# PDB_MH.net
KiCad netlist of a schematic drawn in EAGLE
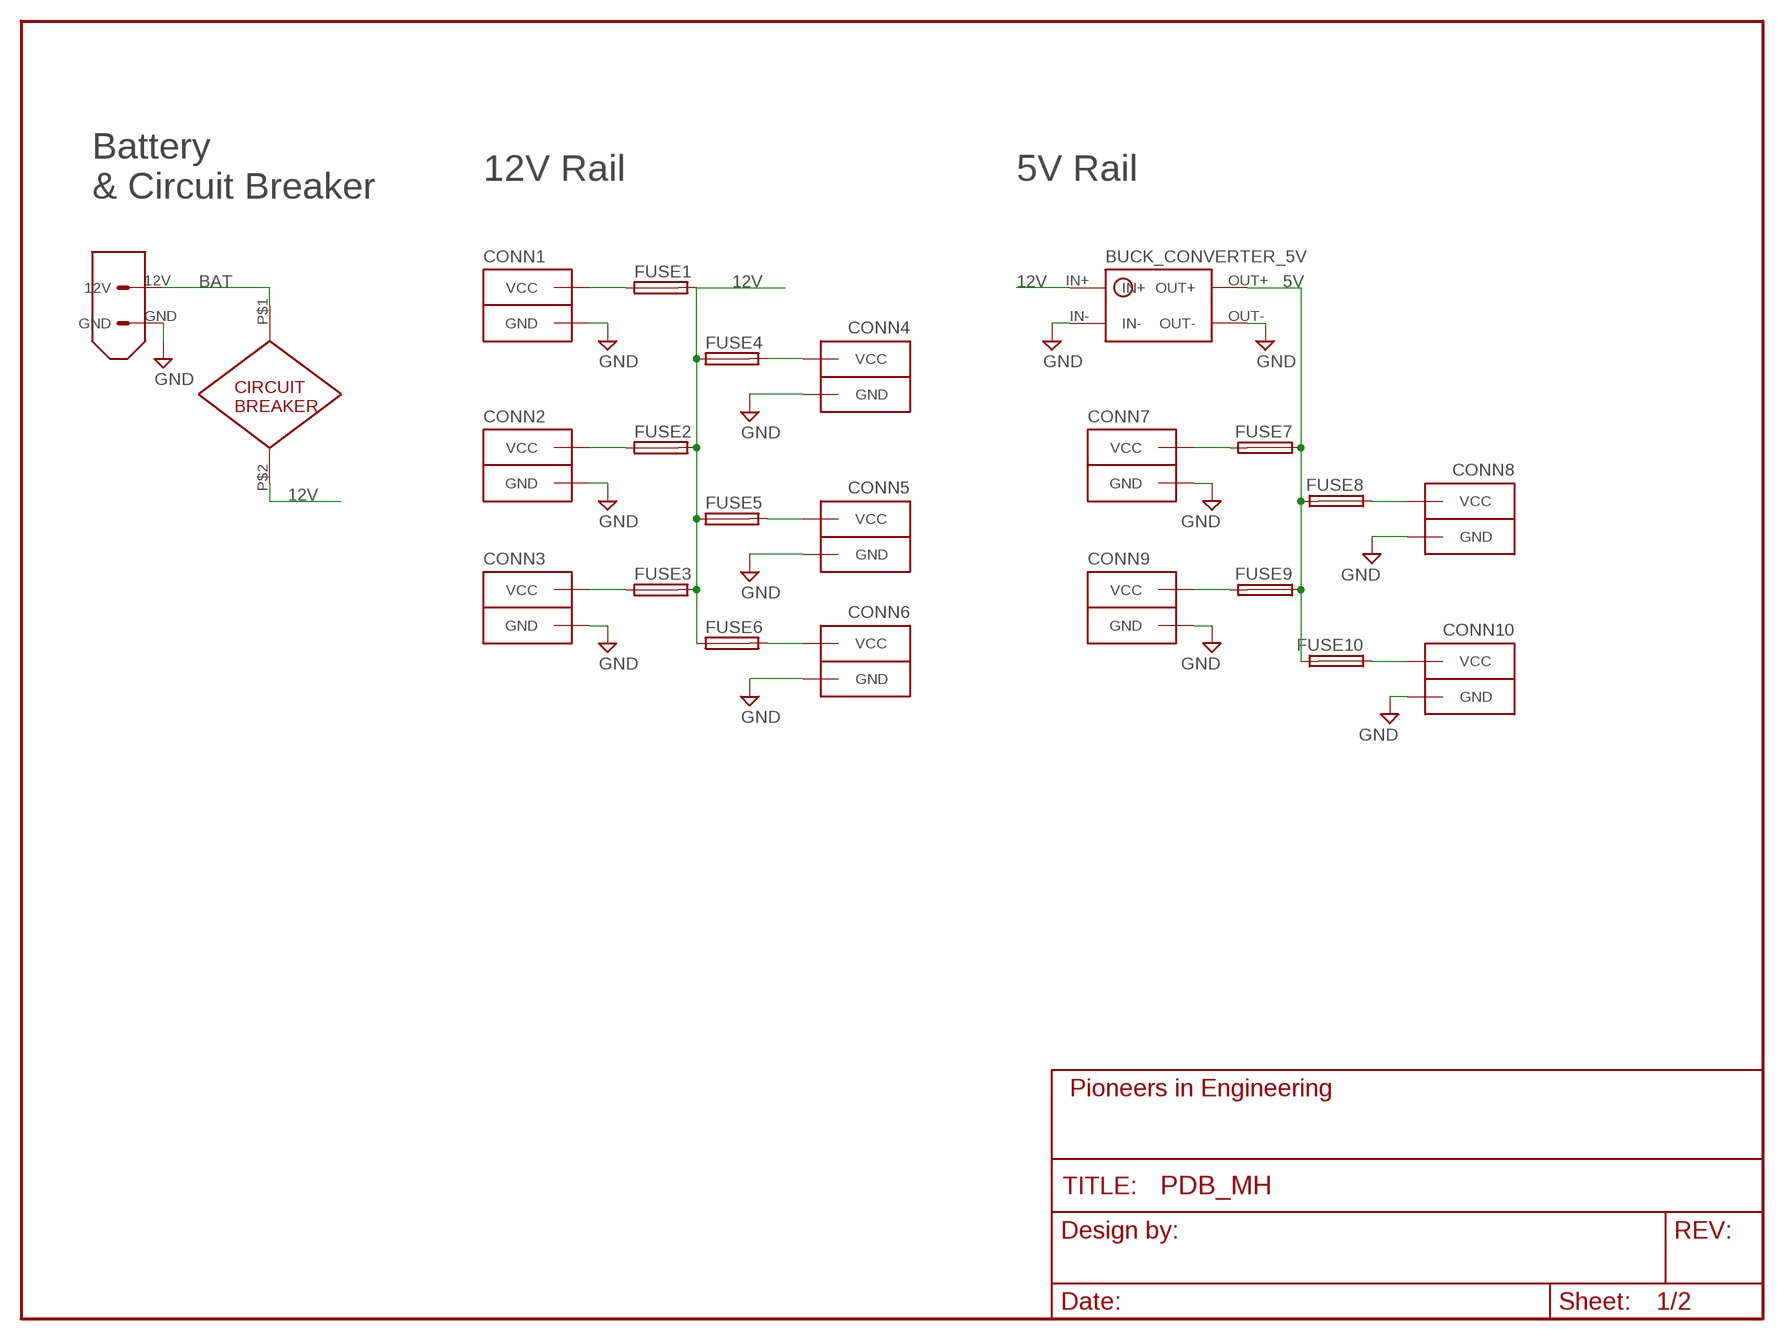
[diagram p0: schematic, sheet 1]
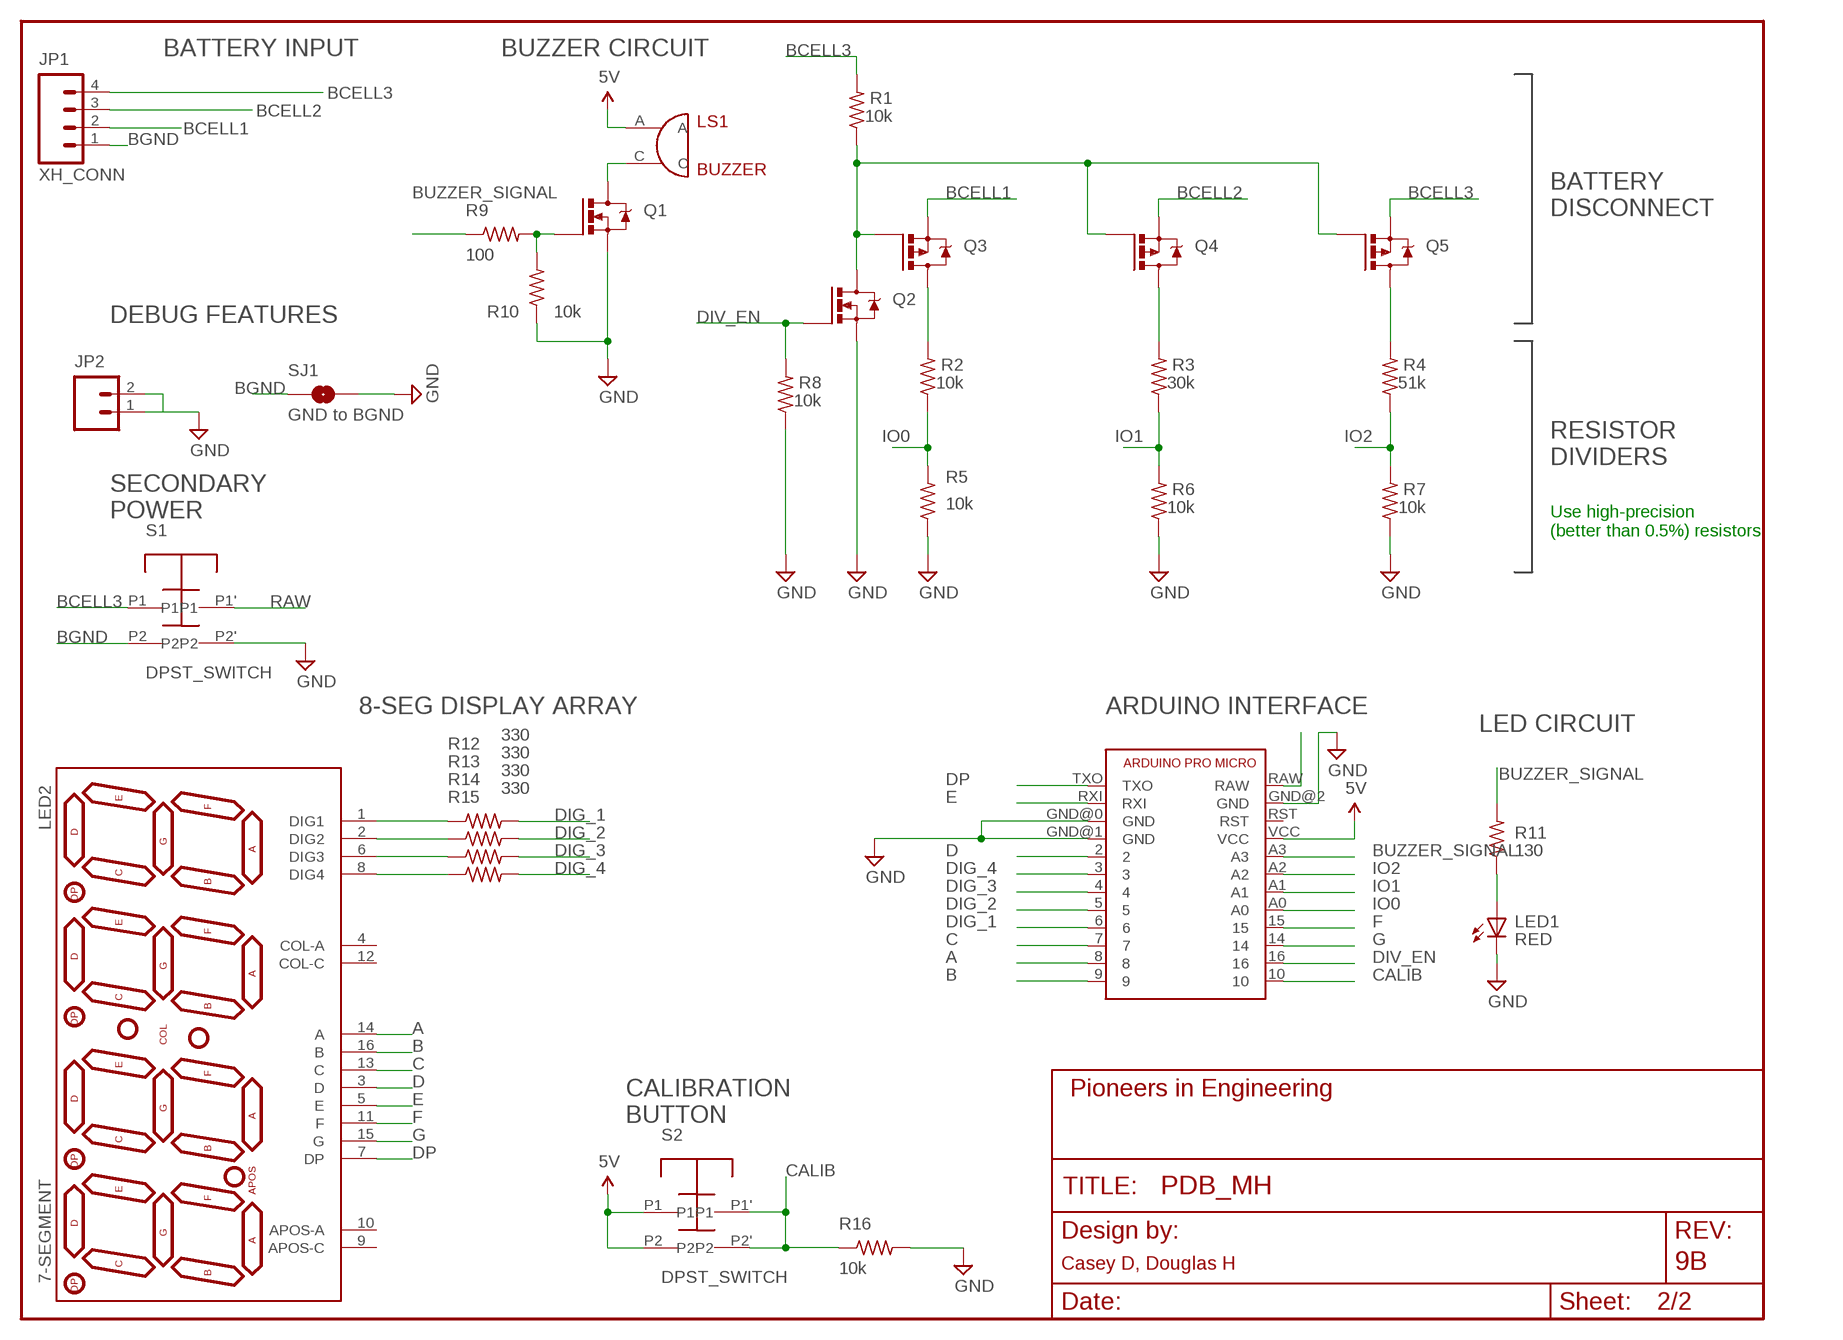
[diagram p1: schematic, sheet 2]

(export (version "E")
  (design (tool "Eeschema 10.0.6"))
  (components
    (comp (ref "CIRCUIT_BREAKER")
      (value "CIRC_BREAKER")
      (footprint "eagle-import:CIRC_BREAKER")
      (libsource (lib "eagle-import") (part "CIRC_BREAKER"))
    )
    (comp (ref "CONN1")
      (value "ANDERSONVERTICAL")
      (footprint "eagle-import:ANDERSON_VERTICAL")
      (libsource (lib "eagle-import") (part "ANDERSONVERTICAL"))
    )
    (comp (ref "CONN2")
      (value "ANDERSONVERTICAL")
      (footprint "eagle-import:ANDERSON_VERTICAL")
      (libsource (lib "eagle-import") (part "ANDERSONVERTICAL"))
    )
    (comp (ref "CONN3")
      (value "ANDERSONVERTICAL")
      (footprint "eagle-import:ANDERSON_VERTICAL")
      (libsource (lib "eagle-import") (part "ANDERSONVERTICAL"))
    )
    (comp (ref "CONN4")
      (value "ANDERSONVERTICAL")
      (footprint "eagle-import:ANDERSON_VERTICAL")
      (libsource (lib "eagle-import") (part "ANDERSONVERTICAL"))
    )
    (comp (ref "CONN5")
      (value "ANDERSONVERTICAL")
      (footprint "eagle-import:ANDERSON_VERTICAL")
      (libsource (lib "eagle-import") (part "ANDERSONVERTICAL"))
    )
    (comp (ref "CONN6")
      (value "ANDERSONVERTICAL")
      (footprint "eagle-import:ANDERSON_VERTICAL")
      (libsource (lib "eagle-import") (part "ANDERSONVERTICAL"))
    )
    (comp (ref "CONN7")
      (value "ANDERSONVERTICAL")
      (footprint "eagle-import:ANDERSON_VERTICAL")
      (libsource (lib "eagle-import") (part "ANDERSONVERTICAL"))
    )
    (comp (ref "CONN8")
      (value "ANDERSONVERTICAL")
      (footprint "eagle-import:ANDERSON_VERTICAL")
      (libsource (lib "eagle-import") (part "ANDERSONVERTICAL"))
    )
    (comp (ref "CONN9")
      (value "ANDERSONVERTICAL")
      (footprint "eagle-import:ANDERSON_VERTICAL")
      (libsource (lib "eagle-import") (part "ANDERSONVERTICAL"))
    )
    (comp (ref "CONN10")
      (value "ANDERSONVERTICAL")
      (footprint "eagle-import:ANDERSON_VERTICAL")
      (libsource (lib "eagle-import") (part "ANDERSONVERTICAL"))
    )
    (comp (ref "FUSE1")
      (value "FUSE_HOLDER_SMD")
      (footprint "eagle-import:FUSE_HOLDER_SMD")
      (libsource (lib "eagle-import") (part "FUSE_HOLDER_SMD"))
    )
    (comp (ref "FUSE2")
      (value "FUSE_HOLDER_SMD")
      (footprint "eagle-import:FUSE_HOLDER_SMD")
      (libsource (lib "eagle-import") (part "FUSE_HOLDER_SMD"))
    )
    (comp (ref "FUSE3")
      (value "FUSE_HOLDER_SMD")
      (footprint "eagle-import:FUSE_HOLDER_SMD")
      (libsource (lib "eagle-import") (part "FUSE_HOLDER_SMD"))
    )
    (comp (ref "FUSE4")
      (value "FUSE_HOLDER_SMD")
      (footprint "eagle-import:FUSE_HOLDER_SMD")
      (libsource (lib "eagle-import") (part "FUSE_HOLDER_SMD"))
    )
    (comp (ref "FUSE5")
      (value "FUSE_HOLDER_SMD")
      (footprint "eagle-import:FUSE_HOLDER_SMD")
      (libsource (lib "eagle-import") (part "FUSE_HOLDER_SMD"))
    )
    (comp (ref "FUSE6")
      (value "FUSE_HOLDER_SMD")
      (footprint "eagle-import:FUSE_HOLDER_SMD")
      (libsource (lib "eagle-import") (part "FUSE_HOLDER_SMD"))
    )
    (comp (ref "FUSE7")
      (value "FUSE_HOLDER_SMD")
      (footprint "eagle-import:FUSE_HOLDER_SMD")
      (libsource (lib "eagle-import") (part "FUSE_HOLDER_SMD"))
    )
    (comp (ref "FUSE8")
      (value "FUSE_HOLDER_SMD")
      (footprint "eagle-import:FUSE_HOLDER_SMD")
      (libsource (lib "eagle-import") (part "FUSE_HOLDER_SMD"))
    )
    (comp (ref "FUSE9")
      (value "FUSE_HOLDER_SMD")
      (footprint "eagle-import:FUSE_HOLDER_SMD")
      (libsource (lib "eagle-import") (part "FUSE_HOLDER_SMD"))
    )
    (comp (ref "FUSE10")
      (value "FUSE_HOLDER_SMD")
      (footprint "eagle-import:FUSE_HOLDER_SMD")
      (libsource (lib "eagle-import") (part "FUSE_HOLDER_SMD"))
    )
    (comp (ref "U$7")
      (value "BUCK_CONVERTER_5V")
      (footprint "eagle-import:BUCK_CONVERTER_5V")
      (libsource (lib "eagle-import") (part "BUCK_CONVERTER_5V"))
    )
    (comp (ref "XT60")
      (value "XT60CONNECTOR")
      (footprint "eagle-import:XT60CONNECTOR")
      (fields (field (name "PARTNUMBER") "PRT-10474 "))
      (libsource (lib "eagle-import") (part "XT60CONNECTOR"))
    )
    (comp (ref "JP1")
      (value "XH_CONN")
      (footprint "eagle-import:XH_CONNECTOR_4POS_2.5MM")
      (libsource (lib "eagle-import") (part "XH_CONNECTOR_4POS"))
    )
    (comp (ref "JP2")
      (value "M02PTH")
      (footprint "eagle-import:1X02")
      (libsource (lib "eagle-import") (part "M02PTH"))
    )
    (comp (ref "LED1")
      (value "RED")
      (footprint "eagle-import:LED-0805")
      (libsource (lib "eagle-import") (part "LED0805"))
    )
    (comp (ref "LED2")
      (value "7-SEGMENT")
      (footprint "eagle-import:7-SEGMENT-4DIGIT-YOUNGSUN")
      (libsource (lib "eagle-import") (part "7-SEGMENT-4DIGIT-YOUNGSUN"))
    )
    (comp (ref "LS1")
      (value "BUZZER")
      (footprint "eagle-import:BUZZER_MAGNETIC_5V_12MM_RADIAL")
      (libsource (lib "eagle-import") (part "BUZZER"))
    )
    (comp (ref "Q1")
      (value "IRFML8244")
      (footprint "eagle-import:SOT23-3")
      (libsource (lib "eagle-import") (part "N-CHANNEL-MOSFETSOT23-3"))
    )
    (comp (ref "Q2")
      (value "IRFML8244")
      (footprint "eagle-import:SOT23-3")
      (libsource (lib "eagle-import") (part "N-CHANNEL-MOSFETSOT23-3"))
    )
    (comp (ref "Q3")
      (value "PMOSFET")
      (footprint "eagle-import:SOT23-3")
      (libsource (lib "eagle-import") (part "P-CHANNEL-MOSFETSOT23-3"))
    )
    (comp (ref "Q4")
      (value "P-CHANNEL-MOSFETSOT23-3")
      (footprint "eagle-import:SOT23-3")
      (libsource (lib "eagle-import") (part "P-CHANNEL-MOSFETSOT23-3"))
    )
    (comp (ref "Q5")
      (value "P-CHANNEL-MOSFETSOT23-3")
      (footprint "eagle-import:SOT23-3")
      (libsource (lib "eagle-import") (part "P-CHANNEL-MOSFETSOT23-3"))
    )
    (comp (ref "R1")
      (value "10k")
      (footprint "eagle-import:R0603")
      (libsource (lib "eagle-import") (part "R-US_R0603"))
    )
    (comp (ref "R2")
      (value "10k")
      (footprint "eagle-import:R0603")
      (libsource (lib "eagle-import") (part "R-US_R0603"))
    )
    (comp (ref "R3")
      (value "30k")
      (footprint "eagle-import:R0603")
      (libsource (lib "eagle-import") (part "R-US_R0603"))
    )
    (comp (ref "R4")
      (value "51k")
      (footprint "eagle-import:R0603")
      (libsource (lib "eagle-import") (part "R-US_R0603"))
    )
    (comp (ref "R5")
      (value "10k")
      (footprint "eagle-import:R0603")
      (libsource (lib "eagle-import") (part "R-US_R0603"))
    )
    (comp (ref "R6")
      (value "10k")
      (footprint "eagle-import:R0603")
      (libsource (lib "eagle-import") (part "R-US_R0603"))
    )
    (comp (ref "R7")
      (value "10k")
      (footprint "eagle-import:R0603")
      (libsource (lib "eagle-import") (part "R-US_R0603"))
    )
    (comp (ref "R8")
      (value "10k")
      (footprint "eagle-import:R0603")
      (libsource (lib "eagle-import") (part "R-US_R0603"))
    )
    (comp (ref "R9")
      (value "100")
      (footprint "eagle-import:R0603")
      (libsource (lib "eagle-import") (part "R-US_R0603"))
    )
    (comp (ref "R10")
      (value "10k")
      (footprint "eagle-import:R0603")
      (libsource (lib "eagle-import") (part "R-US_R0603"))
    )
    (comp (ref "R11")
      (value "130")
      (footprint "eagle-import:R0603")
      (libsource (lib "eagle-import") (part "R-US_R0603"))
    )
    (comp (ref "R12")
      (value "330")
      (footprint "eagle-import:R0603")
      (libsource (lib "eagle-import") (part "R-US_R0603"))
    )
    (comp (ref "R13")
      (value "330")
      (footprint "eagle-import:R0603")
      (libsource (lib "eagle-import") (part "R-US_R0603"))
    )
    (comp (ref "R14")
      (value "330")
      (footprint "eagle-import:R0603")
      (libsource (lib "eagle-import") (part "R-US_R0603"))
    )
    (comp (ref "R15")
      (value "330")
      (footprint "eagle-import:R0603")
      (libsource (lib "eagle-import") (part "R-US_R0603"))
    )
    (comp (ref "R16")
      (value "10k")
      (footprint "eagle-import:R0603")
      (libsource (lib "eagle-import") (part "R-US_R0603"))
    )
    (comp (ref "S1")
      (value "DPST_SWITCH")
      (footprint "eagle-import:C&K_SWITCH")
      (libsource (lib "eagle-import") (part "DPST_SWITCH"))
    )
    (comp (ref "S2")
      (value "DPST_SWITCH")
      (footprint "eagle-import:C&K_SWITCH")
      (libsource (lib "eagle-import") (part "DPST_SWITCH"))
    )
    (comp (ref "SJ1")
      (value "GND to BGND")
      (footprint "eagle-import:SJ_2S-NO")
      (libsource (lib "eagle-import") (part "SOLDERJUMPERNO"))
    )
    (comp (ref "UC1")
      (value "ARDUINO_PRO_MICRO")
      (footprint "eagle-import:ARDUINO_PRO_MICRO")
      (libsource (lib "eagle-import") (part "ARDUINO_PRO_MICRO"))
    )
  )
  (nets
    (net (code "1") (name "5V") (class "Default")
      (node (ref "FUSE10") (pin "P$2_DOWN") (pinfunction "2_P$2_DOWN") (pintype "passive"))
      (node (ref "FUSE10") (pin "P$2_UP") (pinfunction "2_P$2_UP") (pintype "passive"))
      (node (ref "FUSE7") (pin "P$1_DOWN") (pinfunction "1_P$1_DOWN") (pintype "passive"))
      (node (ref "FUSE7") (pin "P$1_UP") (pinfunction "1_P$1_UP") (pintype "passive"))
      (node (ref "FUSE8") (pin "P$2_DOWN") (pinfunction "2_P$2_DOWN") (pintype "passive"))
      (node (ref "FUSE8") (pin "P$2_UP") (pinfunction "2_P$2_UP") (pintype "passive"))
      (node (ref "FUSE9") (pin "P$1_DOWN") (pinfunction "1_P$1_DOWN") (pintype "passive"))
      (node (ref "FUSE9") (pin "P$1_UP") (pinfunction "1_P$1_UP") (pintype "passive"))
      (node (ref "LS1") (pin "A") (pinfunction "A_A") (pintype "bidirectional"))
      (node (ref "S2") (pin "P1") (pinfunction "P1_P1") (pintype "bidirectional"))
      (node (ref "S2") (pin "P2") (pinfunction "P2_P2") (pintype "bidirectional"))
      (node (ref "U$7") (pin "OUT+") (pinfunction "OUT+_OUT+") (pintype "bidirectional"))
      (node (ref "UC1") (pin "VCC") (pinfunction "VCC_VCC") (pintype "bidirectional"))
    )
    (net (code "2") (name "12V") (class "Default")
      (node (ref "CIRCUIT_BREAKER") (pin "P$2") (pinfunction "P$2_P$2") (pintype "bidirectional"))
      (node (ref "FUSE1") (pin "P$2_DOWN") (pinfunction "2_P$2_DOWN") (pintype "passive"))
      (node (ref "FUSE1") (pin "P$2_UP") (pinfunction "2_P$2_UP") (pintype "passive"))
      (node (ref "FUSE2") (pin "P$2_DOWN") (pinfunction "2_P$2_DOWN") (pintype "passive"))
      (node (ref "FUSE2") (pin "P$2_UP") (pinfunction "2_P$2_UP") (pintype "passive"))
      (node (ref "FUSE3") (pin "P$2_DOWN") (pinfunction "2_P$2_DOWN") (pintype "passive"))
      (node (ref "FUSE3") (pin "P$2_UP") (pinfunction "2_P$2_UP") (pintype "passive"))
      (node (ref "FUSE4") (pin "P$1_DOWN") (pinfunction "1_P$1_DOWN") (pintype "passive"))
      (node (ref "FUSE4") (pin "P$1_UP") (pinfunction "1_P$1_UP") (pintype "passive"))
      (node (ref "FUSE5") (pin "P$1_DOWN") (pinfunction "1_P$1_DOWN") (pintype "passive"))
      (node (ref "FUSE5") (pin "P$1_UP") (pinfunction "1_P$1_UP") (pintype "passive"))
      (node (ref "FUSE6") (pin "P$1_DOWN") (pinfunction "1_P$1_DOWN") (pintype "passive"))
      (node (ref "FUSE6") (pin "P$1_UP") (pinfunction "1_P$1_UP") (pintype "passive"))
      (node (ref "U$7") (pin "IN+") (pinfunction "IN+_IN+") (pintype "bidirectional"))
    )
    (net (code "3") (name "A") (class "Default")
      (node (ref "LED2") (pin "14") (pinfunction "A_14") (pintype "bidirectional"))
      (node (ref "UC1") (pin "8") (pinfunction "8_8") (pintype "bidirectional"))
    )
    (net (code "4") (name "B") (class "Default")
      (node (ref "LED2") (pin "16") (pinfunction "B_16") (pintype "bidirectional"))
      (node (ref "UC1") (pin "9") (pinfunction "9_9") (pintype "bidirectional"))
    )
    (net (code "5") (name "BAT") (class "Default")
      (node (ref "CIRCUIT_BREAKER") (pin "P$1") (pinfunction "P$1_P$1") (pintype "bidirectional"))
      (node (ref "XT60") (pin "12V") (pinfunction "12V_12V") (pintype "bidirectional"))
    )
    (net (code "6") (name "BCELL1") (class "Default")
      (node (ref "JP1") (pin "2") (pinfunction "2_2") (pintype "passive"))
      (node (ref "Q3") (pin "2") (pinfunction "S_2") (pintype "passive"))
    )
    (net (code "7") (name "BCELL2") (class "Default")
      (node (ref "JP1") (pin "3") (pinfunction "3_3") (pintype "passive"))
      (node (ref "Q4") (pin "2") (pinfunction "S_2") (pintype "passive"))
    )
    (net (code "8") (name "BCELL3") (class "Default")
      (node (ref "JP1") (pin "4") (pinfunction "4_4") (pintype "passive"))
      (node (ref "Q5") (pin "2") (pinfunction "S_2") (pintype "passive"))
      (node (ref "R1") (pin "2") (pinfunction "2_2") (pintype "passive"))
      (node (ref "S1") (pin "P1") (pinfunction "P1_P1") (pintype "bidirectional"))
    )
    (net (code "9") (name "BGND") (class "Default")
      (node (ref "JP1") (pin "1") (pinfunction "1_1") (pintype "passive"))
      (node (ref "S1") (pin "P2") (pinfunction "P2_P2") (pintype "bidirectional"))
      (node (ref "SJ1") (pin "1") (pinfunction "1_1") (pintype "passive"))
    )
    (net (code "10") (name "BUZZER_SIGNAL") (class "Default")
      (node (ref "R11") (pin "2") (pinfunction "2_2") (pintype "passive"))
      (node (ref "R9") (pin "1") (pinfunction "1_1") (pintype "passive"))
      (node (ref "UC1") (pin "A3") (pinfunction "A3_A3") (pintype "bidirectional"))
    )
    (net (code "11") (name "C") (class "Default")
      (node (ref "LED2") (pin "13") (pinfunction "C_13") (pintype "bidirectional"))
      (node (ref "UC1") (pin "7") (pinfunction "7_7") (pintype "bidirectional"))
    )
    (net (code "12") (name "CALIB") (class "Default")
      (node (ref "R16") (pin "1") (pinfunction "1_1") (pintype "passive"))
      (node (ref "S2") (pin "P1'") (pinfunction "P1'_P1'") (pintype "bidirectional"))
      (node (ref "S2") (pin "P2'") (pinfunction "P2'_P2'") (pintype "bidirectional"))
      (node (ref "UC1") (pin "10") (pinfunction "10_10") (pintype "bidirectional"))
    )
    (net (code "13") (name "D") (class "Default")
      (node (ref "LED2") (pin "3") (pinfunction "D_3") (pintype "bidirectional"))
      (node (ref "UC1") (pin "2") (pinfunction "2_2") (pintype "bidirectional"))
    )
    (net (code "14") (name "DIG_1") (class "Default")
      (node (ref "R12") (pin "2") (pinfunction "2_2") (pintype "passive"))
      (node (ref "UC1") (pin "6") (pinfunction "6_6") (pintype "bidirectional"))
    )
    (net (code "15") (name "DIG_2") (class "Default")
      (node (ref "R13") (pin "2") (pinfunction "2_2") (pintype "passive"))
      (node (ref "UC1") (pin "5") (pinfunction "5_5") (pintype "bidirectional"))
    )
    (net (code "16") (name "DIG_3") (class "Default")
      (node (ref "R14") (pin "2") (pinfunction "2_2") (pintype "passive"))
      (node (ref "UC1") (pin "4") (pinfunction "4_4") (pintype "bidirectional"))
    )
    (net (code "17") (name "DIG_4") (class "Default")
      (node (ref "R15") (pin "2") (pinfunction "2_2") (pintype "passive"))
      (node (ref "UC1") (pin "3") (pinfunction "3_3") (pintype "bidirectional"))
    )
    (net (code "18") (name "DIV_EN") (class "Default")
      (node (ref "Q2") (pin "1") (pinfunction "G_1") (pintype "passive"))
      (node (ref "R8") (pin "2") (pinfunction "2_2") (pintype "passive"))
      (node (ref "UC1") (pin "16") (pinfunction "16_16") (pintype "bidirectional"))
    )
    (net (code "19") (name "DP") (class "Default")
      (node (ref "LED2") (pin "7") (pinfunction "DP_7") (pintype "bidirectional"))
      (node (ref "UC1") (pin "TXO") (pinfunction "TXO_TXO") (pintype "bidirectional"))
    )
    (net (code "20") (name "E") (class "Default")
      (node (ref "LED2") (pin "5") (pinfunction "E_5") (pintype "bidirectional"))
      (node (ref "UC1") (pin "RXI") (pinfunction "RXI_RXI") (pintype "bidirectional"))
    )
    (net (code "21") (name "F") (class "Default")
      (node (ref "LED2") (pin "11") (pinfunction "F_11") (pintype "bidirectional"))
      (node (ref "UC1") (pin "15") (pinfunction "15_15") (pintype "bidirectional"))
    )
    (net (code "22") (name "G") (class "Default")
      (node (ref "LED2") (pin "15") (pinfunction "G_15") (pintype "bidirectional"))
      (node (ref "UC1") (pin "14") (pinfunction "14_14") (pintype "bidirectional"))
    )
    (net (code "23") (name "GND") (class "Default")
      (node (ref "CONN1") (pin "PIN1") (pinfunction "GND_PIN1") (pintype "bidirectional"))
      (node (ref "CONN10") (pin "PIN1") (pinfunction "GND_PIN1") (pintype "bidirectional"))
      (node (ref "CONN2") (pin "PIN1") (pinfunction "GND_PIN1") (pintype "bidirectional"))
      (node (ref "CONN3") (pin "PIN1") (pinfunction "GND_PIN1") (pintype "bidirectional"))
      (node (ref "CONN4") (pin "PIN1") (pinfunction "GND_PIN1") (pintype "bidirectional"))
      (node (ref "CONN5") (pin "PIN1") (pinfunction "GND_PIN1") (pintype "bidirectional"))
      (node (ref "CONN6") (pin "PIN1") (pinfunction "GND_PIN1") (pintype "bidirectional"))
      (node (ref "CONN7") (pin "PIN1") (pinfunction "GND_PIN1") (pintype "bidirectional"))
      (node (ref "CONN8") (pin "PIN1") (pinfunction "GND_PIN1") (pintype "bidirectional"))
      (node (ref "CONN9") (pin "PIN1") (pinfunction "GND_PIN1") (pintype "bidirectional"))
      (node (ref "JP2") (pin "1") (pinfunction "1_1") (pintype "passive"))
      (node (ref "JP2") (pin "2") (pinfunction "2_2") (pintype "passive"))
      (node (ref "LED1") (pin "C") (pinfunction "C_C") (pintype "passive"))
      (node (ref "Q1") (pin "2") (pinfunction "S_2") (pintype "passive"))
      (node (ref "Q2") (pin "2") (pinfunction "S_2") (pintype "passive"))
      (node (ref "R10") (pin "1") (pinfunction "1_1") (pintype "passive"))
      (node (ref "R16") (pin "2") (pinfunction "2_2") (pintype "passive"))
      (node (ref "R5") (pin "1") (pinfunction "1_1") (pintype "passive"))
      (node (ref "R6") (pin "1") (pinfunction "1_1") (pintype "passive"))
      (node (ref "R7") (pin "1") (pinfunction "1_1") (pintype "passive"))
      (node (ref "R8") (pin "1") (pinfunction "1_1") (pintype "passive"))
      (node (ref "S1") (pin "P2'") (pinfunction "P2'_P2'") (pintype "bidirectional"))
      (node (ref "SJ1") (pin "2") (pinfunction "2_2") (pintype "passive"))
      (node (ref "U$7") (pin "IN-") (pinfunction "IN-_IN-") (pintype "bidirectional"))
      (node (ref "U$7") (pin "OUT-") (pinfunction "OUT-_OUT-") (pintype "bidirectional"))
      (node (ref "UC1") (pin "GND@0") (pinfunction "GND_GND@0") (pintype "bidirectional"))
      (node (ref "UC1") (pin "GND@1") (pinfunction "GND_GND@1") (pintype "bidirectional"))
      (node (ref "UC1") (pin "GND@2") (pinfunction "GND_GND@2") (pintype "bidirectional"))
      (node (ref "XT60") (pin "GND") (pinfunction "GND_GND") (pintype "bidirectional"))
    )
    (net (code "24") (name "IO0") (class "Default")
      (node (ref "R2") (pin "1") (pinfunction "1_1") (pintype "passive"))
      (node (ref "R5") (pin "2") (pinfunction "2_2") (pintype "passive"))
      (node (ref "UC1") (pin "A0") (pinfunction "A0_A0") (pintype "bidirectional"))
    )
    (net (code "25") (name "IO1") (class "Default")
      (node (ref "R3") (pin "1") (pinfunction "1_1") (pintype "passive"))
      (node (ref "R6") (pin "2") (pinfunction "2_2") (pintype "passive"))
      (node (ref "UC1") (pin "A1") (pinfunction "A1_A1") (pintype "bidirectional"))
    )
    (net (code "26") (name "IO2") (class "Default")
      (node (ref "R4") (pin "1") (pinfunction "1_1") (pintype "passive"))
      (node (ref "R7") (pin "2") (pinfunction "2_2") (pintype "passive"))
      (node (ref "UC1") (pin "A2") (pinfunction "A2_A2") (pintype "bidirectional"))
    )
    (net (code "27") (name "Net-(CONN1-VCC)") (class "Default")
      (node (ref "CONN1") (pin "PIN2") (pinfunction "VCC_PIN2") (pintype "bidirectional"))
      (node (ref "FUSE1") (pin "P$1_DOWN") (pinfunction "1_P$1_DOWN") (pintype "passive"))
      (node (ref "FUSE1") (pin "P$1_UP") (pinfunction "1_P$1_UP") (pintype "passive"))
    )
    (net (code "28") (name "Net-(CONN2-VCC)") (class "Default")
      (node (ref "CONN2") (pin "PIN2") (pinfunction "VCC_PIN2") (pintype "bidirectional"))
      (node (ref "FUSE2") (pin "P$1_DOWN") (pinfunction "1_P$1_DOWN") (pintype "passive"))
      (node (ref "FUSE2") (pin "P$1_UP") (pinfunction "1_P$1_UP") (pintype "passive"))
    )
    (net (code "29") (name "Net-(CONN3-VCC)") (class "Default")
      (node (ref "CONN3") (pin "PIN2") (pinfunction "VCC_PIN2") (pintype "bidirectional"))
      (node (ref "FUSE3") (pin "P$1_DOWN") (pinfunction "1_P$1_DOWN") (pintype "passive"))
      (node (ref "FUSE3") (pin "P$1_UP") (pinfunction "1_P$1_UP") (pintype "passive"))
    )
    (net (code "30") (name "Net-(CONN4-VCC)") (class "Default")
      (node (ref "CONN4") (pin "PIN2") (pinfunction "VCC_PIN2") (pintype "bidirectional"))
      (node (ref "FUSE4") (pin "P$2_DOWN") (pinfunction "2_P$2_DOWN") (pintype "passive"))
      (node (ref "FUSE4") (pin "P$2_UP") (pinfunction "2_P$2_UP") (pintype "passive"))
    )
    (net (code "31") (name "Net-(CONN5-VCC)") (class "Default")
      (node (ref "CONN5") (pin "PIN2") (pinfunction "VCC_PIN2") (pintype "bidirectional"))
      (node (ref "FUSE5") (pin "P$2_DOWN") (pinfunction "2_P$2_DOWN") (pintype "passive"))
      (node (ref "FUSE5") (pin "P$2_UP") (pinfunction "2_P$2_UP") (pintype "passive"))
    )
    (net (code "32") (name "Net-(CONN6-VCC)") (class "Default")
      (node (ref "CONN6") (pin "PIN2") (pinfunction "VCC_PIN2") (pintype "bidirectional"))
      (node (ref "FUSE6") (pin "P$2_DOWN") (pinfunction "2_P$2_DOWN") (pintype "passive"))
      (node (ref "FUSE6") (pin "P$2_UP") (pinfunction "2_P$2_UP") (pintype "passive"))
    )
    (net (code "33") (name "Net-(CONN7-VCC)") (class "Default")
      (node (ref "CONN7") (pin "PIN2") (pinfunction "VCC_PIN2") (pintype "bidirectional"))
      (node (ref "FUSE7") (pin "P$2_DOWN") (pinfunction "2_P$2_DOWN") (pintype "passive"))
      (node (ref "FUSE7") (pin "P$2_UP") (pinfunction "2_P$2_UP") (pintype "passive"))
    )
    (net (code "34") (name "Net-(CONN8-VCC)") (class "Default")
      (node (ref "CONN8") (pin "PIN2") (pinfunction "VCC_PIN2") (pintype "bidirectional"))
      (node (ref "FUSE8") (pin "P$1_DOWN") (pinfunction "1_P$1_DOWN") (pintype "passive"))
      (node (ref "FUSE8") (pin "P$1_UP") (pinfunction "1_P$1_UP") (pintype "passive"))
    )
    (net (code "35") (name "Net-(CONN9-VCC)") (class "Default")
      (node (ref "CONN9") (pin "PIN2") (pinfunction "VCC_PIN2") (pintype "bidirectional"))
      (node (ref "FUSE9") (pin "P$2_DOWN") (pinfunction "2_P$2_DOWN") (pintype "passive"))
      (node (ref "FUSE9") (pin "P$2_UP") (pinfunction "2_P$2_UP") (pintype "passive"))
    )
    (net (code "36") (name "Net-(CONN10-VCC)") (class "Default")
      (node (ref "CONN10") (pin "PIN2") (pinfunction "VCC_PIN2") (pintype "bidirectional"))
      (node (ref "FUSE10") (pin "P$1_DOWN") (pinfunction "1_P$1_DOWN") (pintype "passive"))
      (node (ref "FUSE10") (pin "P$1_UP") (pinfunction "1_P$1_UP") (pintype "passive"))
    )
    (net (code "37") (name "Net-(LED1-PadA)") (class "Default")
      (node (ref "LED1") (pin "A") (pinfunction "A_A") (pintype "passive"))
      (node (ref "R11") (pin "1") (pinfunction "1_1") (pintype "passive"))
    )
    (net (code "38") (name "Net-(LED2-DIG1)") (class "Default")
      (node (ref "LED2") (pin "1") (pinfunction "DIG1_1") (pintype "bidirectional"))
      (node (ref "R12") (pin "1") (pinfunction "1_1") (pintype "passive"))
    )
    (net (code "39") (name "Net-(LED2-DIG2)") (class "Default")
      (node (ref "LED2") (pin "2") (pinfunction "DIG2_2") (pintype "bidirectional"))
      (node (ref "R13") (pin "1") (pinfunction "1_1") (pintype "passive"))
    )
    (net (code "40") (name "Net-(LED2-DIG3)") (class "Default")
      (node (ref "LED2") (pin "6") (pinfunction "DIG3_6") (pintype "bidirectional"))
      (node (ref "R14") (pin "1") (pinfunction "1_1") (pintype "passive"))
    )
    (net (code "41") (name "Net-(LED2-DIG4)") (class "Default")
      (node (ref "LED2") (pin "8") (pinfunction "DIG4_8") (pintype "bidirectional"))
      (node (ref "R15") (pin "1") (pinfunction "1_1") (pintype "passive"))
    )
    (net (code "42") (name "Net-(Q1-D)") (class "Default")
      (node (ref "LS1") (pin "C") (pinfunction "C_C") (pintype "bidirectional"))
      (node (ref "Q1") (pin "3") (pinfunction "D_3") (pintype "passive"))
    )
    (net (code "43") (name "Net-(Q1-G)") (class "Default")
      (node (ref "Q1") (pin "1") (pinfunction "G_1") (pintype "passive"))
      (node (ref "R10") (pin "2") (pinfunction "2_2") (pintype "passive"))
      (node (ref "R9") (pin "2") (pinfunction "2_2") (pintype "passive"))
    )
    (net (code "44") (name "Net-(Q2-D)") (class "Default")
      (node (ref "Q2") (pin "3") (pinfunction "D_3") (pintype "passive"))
      (node (ref "Q3") (pin "1") (pinfunction "G_1") (pintype "passive"))
      (node (ref "Q4") (pin "1") (pinfunction "G_1") (pintype "passive"))
      (node (ref "Q5") (pin "1") (pinfunction "G_1") (pintype "passive"))
      (node (ref "R1") (pin "1") (pinfunction "1_1") (pintype "passive"))
    )
    (net (code "45") (name "Net-(Q3-D)") (class "Default")
      (node (ref "Q3") (pin "3") (pinfunction "D_3") (pintype "passive"))
      (node (ref "R2") (pin "2") (pinfunction "2_2") (pintype "passive"))
    )
    (net (code "46") (name "Net-(Q4-D)") (class "Default")
      (node (ref "Q4") (pin "3") (pinfunction "D_3") (pintype "passive"))
      (node (ref "R3") (pin "2") (pinfunction "2_2") (pintype "passive"))
    )
    (net (code "47") (name "Net-(Q5-D)") (class "Default")
      (node (ref "Q5") (pin "3") (pinfunction "D_3") (pintype "passive"))
      (node (ref "R4") (pin "2") (pinfunction "2_2") (pintype "passive"))
    )
    (net (code "48") (name "RAW") (class "Default")
      (node (ref "S1") (pin "P1'") (pinfunction "P1'_P1'") (pintype "bidirectional"))
      (node (ref "UC1") (pin "RAW") (pinfunction "RAW_RAW") (pintype "bidirectional"))
    )
    (net (code "49") (name "unconnected-(LED2-APOS-A-Pad10)") (class "Default")
      (node (ref "LED2") (pin "10") (pinfunction "APOS-A_10") (pintype "bidirectional"))
    )
    (net (code "50") (name "unconnected-(LED2-APOS-C-Pad9)") (class "Default")
      (node (ref "LED2") (pin "9") (pinfunction "APOS-C_9") (pintype "bidirectional"))
    )
    (net (code "51") (name "unconnected-(LED2-COL-A-Pad4)") (class "Default")
      (node (ref "LED2") (pin "4") (pinfunction "COL-A_4") (pintype "bidirectional"))
    )
    (net (code "52") (name "unconnected-(LED2-COL-C-Pad12)") (class "Default")
      (node (ref "LED2") (pin "12") (pinfunction "COL-C_12") (pintype "bidirectional"))
    )
    (net (code "53") (name "unconnected-(UC1-PadRST)") (class "Default")
      (node (ref "UC1") (pin "RST") (pinfunction "RST_RST") (pintype "bidirectional"))
    )
  )
)
